# 04_-_Power_Supply.net
KiCad netlist of a schematic drawn in Altium Designer
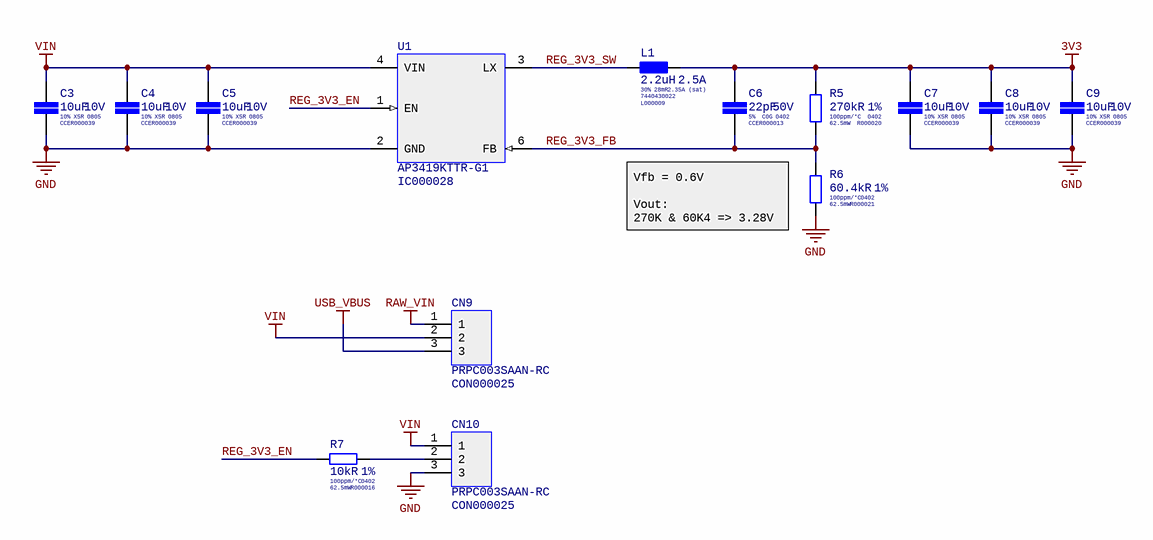
[diagram p0: [04] - Power Supply.SchDoc]

(export (version "E")
  (design (tool "Eeschema 10.0.6"))
  (components
    (comp (ref "C3")
      (value "10uF 10V")
      (footprint "CAP-SMD-0805-1.35MM-IPC-MED")
      (description "CAP CER 10U 10V X5R 10% SMD 0805 85C SAMSUNG")
      (fields
        (field (name "VOLTAGE") "10V")
        (field (name "INTERNAL PART NUMBER") "CCER000039")
        (field (name "TOLERANCE") "10%")
        (field (name "VOLTAGE RATING") "10V")
        (field (name "DIELECTRIC") "X5R")
        (field (name "CASE/PACKAGE") "0805")
        (field (name "CAPACITANCE") "10uF")
      )
      (libsource (lib "Altium_Lib_Standard") (part "CL21A106KPFNNNG"))
    )
    (comp (ref "C4")
      (value "10uF 10V")
      (footprint "CAP-SMD-0805-1.35MM-IPC-MED")
      (description "CAP CER 10U 10V X5R 10% SMD 0805 85C SAMSUNG")
      (fields
        (field (name "VOLTAGE") "10V")
        (field (name "INTERNAL PART NUMBER") "CCER000039")
        (field (name "TOLERANCE") "10%")
        (field (name "VOLTAGE RATING") "10V")
        (field (name "DIELECTRIC") "X5R")
        (field (name "CASE/PACKAGE") "0805")
        (field (name "CAPACITANCE") "10uF")
      )
      (libsource (lib "Altium_Lib_Standard") (part "CL21A106KPFNNNG"))
    )
    (comp (ref "C5")
      (value "10uF 10V")
      (footprint "CAP-SMD-0805-1.35MM-IPC-MED")
      (description "CAP CER 10U 10V X5R 10% SMD 0805 85C SAMSUNG")
      (fields
        (field (name "VOLTAGE") "10V")
        (field (name "INTERNAL PART NUMBER") "CCER000039")
        (field (name "TOLERANCE") "10%")
        (field (name "VOLTAGE RATING") "10V")
        (field (name "DIELECTRIC") "X5R")
        (field (name "CASE/PACKAGE") "0805")
        (field (name "CAPACITANCE") "10uF")
      )
      (libsource (lib "Altium_Lib_Standard") (part "CL21A106KPFNNNG"))
    )
    (comp (ref "C6")
      (value "22pF 50V")
      (footprint "CAP-SMD-0402-0.55MM-IPC-MED")
      (description "CAP CER 22P 50V C0G 5% SMD 0402 125C SAMSUNG")
      (fields
        (field (name "MANUFACTURER") "Samsung")
        (field (name "MANUFACTURER PART NUMBER") "CL05C220JB5NNNC")
        (field (name "INTERNAL PART NUMBER") "CCER000013")
        (field (name "VOLTAGE RATING") "50V")
        (field (name "TOLERANCE") "5%")
        (field (name "DIELECTRIC") "C0G")
        (field (name "CASE/PACKAGE") "0402")
        (field (name "CAPACITANCE") "22pF")
      )
      (libsource (lib "Altium_Lib_Standard") (part "CL05C220JB5NNNC"))
    )
    (comp (ref "C7")
      (value "10uF 10V")
      (footprint "CAP-SMD-0805-1.35MM-IPC-MED")
      (description "CAP CER 10U 10V X5R 10% SMD 0805 85C SAMSUNG")
      (fields
        (field (name "VOLTAGE") "10V")
        (field (name "INTERNAL PART NUMBER") "CCER000039")
        (field (name "TOLERANCE") "10%")
        (field (name "VOLTAGE RATING") "10V")
        (field (name "DIELECTRIC") "X5R")
        (field (name "CASE/PACKAGE") "0805")
        (field (name "CAPACITANCE") "10uF")
      )
      (libsource (lib "Altium_Lib_Standard") (part "CL21A106KPFNNNG"))
    )
    (comp (ref "C8")
      (value "10uF 10V")
      (footprint "CAP-SMD-0805-1.35MM-IPC-MED")
      (description "CAP CER 10U 10V X5R 10% SMD 0805 85C SAMSUNG")
      (fields
        (field (name "VOLTAGE") "10V")
        (field (name "INTERNAL PART NUMBER") "CCER000039")
        (field (name "TOLERANCE") "10%")
        (field (name "VOLTAGE RATING") "10V")
        (field (name "DIELECTRIC") "X5R")
        (field (name "CASE/PACKAGE") "0805")
        (field (name "CAPACITANCE") "10uF")
      )
      (libsource (lib "Altium_Lib_Standard") (part "CL21A106KPFNNNG"))
    )
    (comp (ref "C9")
      (value "10uF 10V")
      (footprint "CAP-SMD-0805-1.35MM-IPC-MED")
      (description "CAP CER 10U 10V X5R 10% SMD 0805 85C SAMSUNG")
      (fields
        (field (name "VOLTAGE") "10V")
        (field (name "INTERNAL PART NUMBER") "CCER000039")
        (field (name "TOLERANCE") "10%")
        (field (name "VOLTAGE RATING") "10V")
        (field (name "DIELECTRIC") "X5R")
        (field (name "CASE/PACKAGE") "0805")
        (field (name "CAPACITANCE") "10uF")
      )
      (libsource (lib "Altium_Lib_Standard") (part "CL21A106KPFNNNG"))
    )
    (comp (ref "CN9")
      (value "PRPC003SAAN-RC")
      (footprint "CON-THT-PINHEADER-2.54MM-3POS-1X3")
      (description "CON PINHDR 2.54MM 1x03")
      (fields (field (name "MANUFACTURER") "Sullins") (field (name "INTERNAL PART NUMBER") "CON000025"))
      (libsource (lib "Altium_Lib_Standard") (part "PRPC003SAAN-RC"))
    )
    (comp (ref "CN10")
      (value "PRPC003SAAN-RC")
      (footprint "CON-THT-PINHEADER-2.54MM-3POS-1X3")
      (description "CON PINHDR 2.54MM 1x03")
      (fields (field (name "MANUFACTURER") "Sullins") (field (name "INTERNAL PART NUMBER") "CON000025"))
      (libsource (lib "Altium_Lib_Standard") (part "PRPC003SAAN-RC"))
    )
    (comp (ref "L1")
      (value "7440430022")
      (footprint "IND-SMD-7440430022-3MM")
      (description "IND 2U2 2A5 28mR 30% SMD FERRITE WURTH")
      (fields
        (field (name "MANUFACTURER") "Wurth Electronics")
        (field (name "TOLERANCE") "30%")
        (field (name "SATURATION CURRENT") "2.35A (sat)")
        (field (name "INTERNAL PART NUMBER") "L000009")
        (field (name "MANUFACTURER PART NUMBER") "7440430022")
        (field (name "INDUCTANCE TOLERANCE") "30%")
        (field (name "DC RESISTANCE (DCR)") "28mR")
        (field (name "CURRENT RATING") "2.5A")
        (field (name "INDUCTANCE") "2.2uH")
      )
      (libsource (lib "Altium_Lib_Standard") (part "7440430022"))
    )
    (comp (ref "R5")
      (value "RC0402FR-07270KL")
      (footprint "RES-SMD-0402-0.4MM-IPC-MED")
      (description "RES 270K 1% 1/16W SMD 0402 YAEGO")
      (fields
        (field (name "MANUFACTURER") "Yageo")
        (field (name "CASE/PACKAGE") "0402")
        (field (name "TOLERANCE") "1%")
        (field (name "TEMPERATURE COEFFICIENT") "100ppm/°C")
        (field (name "RESISTANCE") "270kR")
        (field (name "MAX POWER DISSIPATION") "62.5mW")
        (field (name "INTERNAL PART NUMBER") "R000020")
      )
      (libsource (lib "Altium_Lib_Standard") (part "RC0402FR-07270KL"))
    )
    (comp (ref "R6")
      (value "RC0402FR-0760K4L")
      (footprint "RES-SMD-0402-0.4MM-IPC-MED")
      (description "RES 60K4 1% 1/16W SMD 0402 YAEGO")
      (fields
        (field (name "MANUFACTURER") "Yageo")
        (field (name "RESISTANCE") "60.4kR")
        (field (name "TOLERANCE") "1%")
        (field (name "TEMPERATURE COEFFICIENT") "100ppm/°C")
        (field (name "CASE/PACKAGE") "0402")
        (field (name "POWER RATING") "62.5mW")
        (field (name "INTERNAL PART NUMBER") "R000021")
      )
      (libsource (lib "Altium_Lib_Standard") (part "RC0402FR-0760K4L"))
    )
    (comp (ref "R7")
      (value "10kR 1%")
      (footprint "RES-SMD-0402-0.4MM-IPC-MED")
      (description "RES 10K 1% 1/16W SMD 0402 YAEGO")
      (fields
        (field (name "MANUFACTURER") "Yageo")
        (field (name "MANUFACTURER PART NUMBER") "RC0402FR-0710KL")
        (field (name "TOLERANCE") "1%")
        (field (name "TEMPERATURE COEFFICIENT") "100ppm/°C")
        (field (name "RESISTANCE") "10kR")
        (field (name "POWER RATING") "62.5mW")
        (field (name "CASE CODE (IMPERIAL)") "0402")
        (field (name "INTERNAL PART NUMBER") "R000016")
      )
      (libsource (lib "Altium_Lib_Standard") (part "RC0402FR-0710KL"))
    )
    (comp (ref "U1")
      (value "AP3419KTTR-G1")
      (footprint "SOT-23-6-H1MM-DIODES-INC")
      (description "IC REGULATOR BUCK 2A SYNC 1MHZ SOT-23-6")
      (fields (field (name "MANUFACTURER") "Diodes") (field (name "INTERNAL PART NUMBER") "IC000028"))
      (libsource (lib "Altium_Lib_Standard") (part "AP3419KTTR-G1"))
    )
  )
  (nets
    (net (code "1") (name "/REG_3V3_EN") (class "Default")
      (node (ref "R7") (pin "1") (pinfunction "1_1") (pintype "passive"))
      (node (ref "U1") (pin "1") (pinfunction "EN_1") (pintype "input"))
    )
    (net (code "2") (name "/REG_3V3_FB") (class "Default")
      (node (ref "C6") (pin "2") (pinfunction "2_2") (pintype "passive"))
      (node (ref "R5") (pin "2") (pinfunction "2_2") (pintype "passive"))
      (node (ref "R6") (pin "1") (pinfunction "1_1") (pintype "passive"))
      (node (ref "U1") (pin "6") (pinfunction "FB_6") (pintype "input"))
    )
    (net (code "3") (name "/REG_3V3_SW") (class "Default")
      (node (ref "L1") (pin "1") (pinfunction "1_1") (pintype "passive"))
      (node (ref "U1") (pin "3") (pinfunction "LX_3") (pintype "power_in"))
    )
    (net (code "4") (name "3V3") (class "Default")
      (node (ref "C6") (pin "1") (pinfunction "1_1") (pintype "passive"))
      (node (ref "C7") (pin "1") (pinfunction "1_1") (pintype "passive"))
      (node (ref "C8") (pin "1") (pinfunction "1_1") (pintype "passive"))
      (node (ref "C9") (pin "1") (pinfunction "1_1") (pintype "passive"))
      (node (ref "L1") (pin "2") (pinfunction "2_2") (pintype "passive"))
      (node (ref "R5") (pin "1") (pinfunction "1_1") (pintype "passive"))
    )
    (net (code "5") (name "GND") (class "Default")
      (node (ref "C3") (pin "2") (pinfunction "2_2") (pintype "passive"))
      (node (ref "C4") (pin "2") (pinfunction "2_2") (pintype "passive"))
      (node (ref "C5") (pin "2") (pinfunction "2_2") (pintype "passive"))
      (node (ref "C7") (pin "2") (pinfunction "2_2") (pintype "passive"))
      (node (ref "C8") (pin "2") (pinfunction "2_2") (pintype "passive"))
      (node (ref "C9") (pin "2") (pinfunction "2_2") (pintype "passive"))
      (node (ref "CN10") (pin "3") (pinfunction "3_3") (pintype "passive"))
      (node (ref "R6") (pin "2") (pinfunction "2_2") (pintype "passive"))
      (node (ref "U1") (pin "2") (pinfunction "GND_2") (pintype "power_in"))
    )
    (net (code "6") (name "Net-(CN10-Pad2)") (class "Default")
      (node (ref "CN10") (pin "2") (pinfunction "2_2") (pintype "passive"))
      (node (ref "R7") (pin "2") (pinfunction "2_2") (pintype "passive"))
    )
    (net (code "7") (name "RAW_VIN") (class "Default")
      (node (ref "CN9") (pin "1") (pinfunction "1_1") (pintype "passive"))
    )
    (net (code "8") (name "USB_VBUS") (class "Default")
      (node (ref "CN9") (pin "3") (pinfunction "3_3") (pintype "passive"))
    )
    (net (code "9") (name "VIN") (class "Default")
      (node (ref "C3") (pin "1") (pinfunction "1_1") (pintype "passive"))
      (node (ref "C4") (pin "1") (pinfunction "1_1") (pintype "passive"))
      (node (ref "C5") (pin "1") (pinfunction "1_1") (pintype "passive"))
      (node (ref "CN10") (pin "1") (pinfunction "1_1") (pintype "passive"))
      (node (ref "CN9") (pin "2") (pinfunction "2_2") (pintype "passive"))
      (node (ref "U1") (pin "4") (pinfunction "VIN_4") (pintype "power_in"))
    )
  )
)
